# 6_Power_Fuse_MCU.net
KiCad netlist of a schematic drawn in Altium Designer
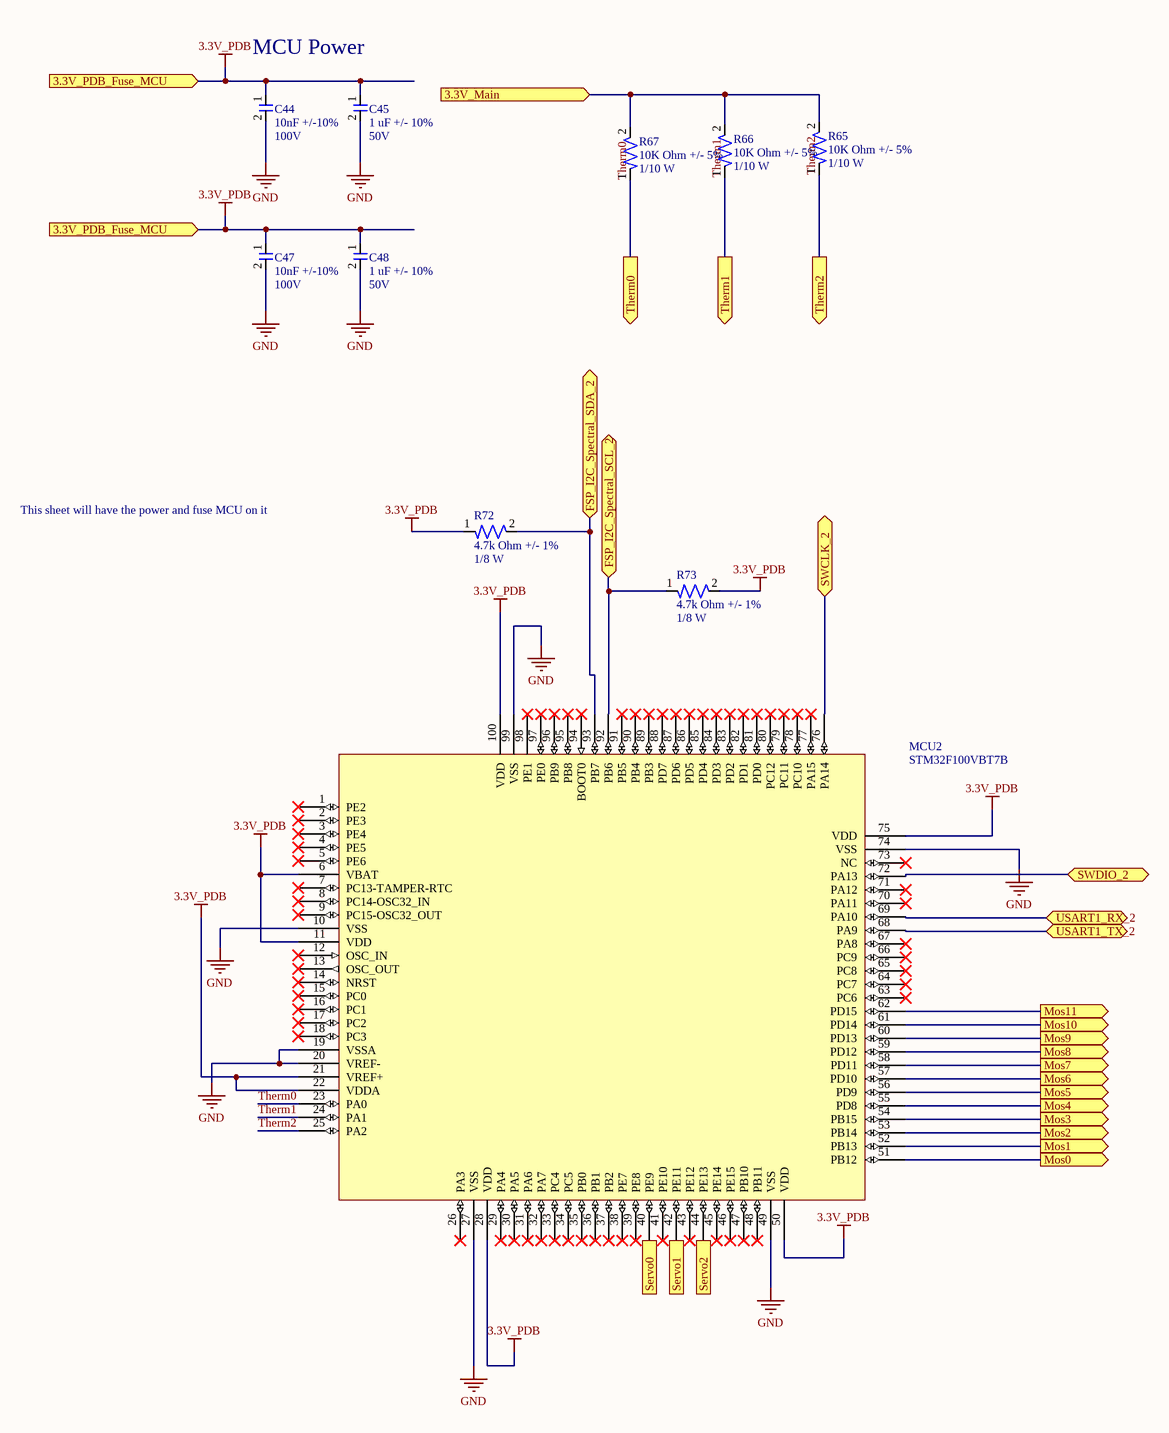
[diagram p0: 6_Power_Fuse_MCU.SchDoc]

(export (version "E")
  (design (tool "Eeschema 10.0.6"))
  (components
    (comp (ref "C44")
      (value "CC0603KRX7R0BB103")
      (footprint "CAP-0603")
      (description "100V 10nF X7R ±10% 0603 Multilayer Ceramic Capacitors MLCC - SMD/SMT ROHS")
      (fields
        (field (name "MANUFACTURER") "Yageo")
        (field (name "JLC PART NUMBER") "C107059")
        (field (name "CAPACITANCE") "10nF +/-10%")
        (field (name "VOLTAGE RATING") "100V")
      )
      (libsource (lib "MasterLib") (part "CAP-10N-0003-JLC"))
    )
    (comp (ref "C45")
      (value "GCM21BR71H105KA03L")
      (footprint "CAP-0805")
      (description "50V 1uF X7R ±10% 0805 Multilayer Ceramic Capacitors MLCC - SMD/SMT ROHS")
      (fields
        (field (name "JLC PART NUMBER") "C126592")
        (field (name "CAP") "1 uF +/- 10%")
        (field (name "VOLTAGE") "50V")
      )
      (libsource (lib "MasterLib") (part "CAP-1U-0003-JLC"))
    )
    (comp (ref "C47")
      (value "CC0603KRX7R0BB103")
      (footprint "CAP-0603")
      (description "100V 10nF X7R ±10% 0603 Multilayer Ceramic Capacitors MLCC - SMD/SMT ROHS")
      (fields
        (field (name "MANUFACTURER") "Yageo")
        (field (name "JLC PART NUMBER") "C107059")
        (field (name "CAPACITANCE") "10nF +/-10%")
        (field (name "VOLTAGE RATING") "100V")
      )
      (libsource (lib "MasterLib") (part "CAP-10N-0003-JLC"))
    )
    (comp (ref "C48")
      (value "GCM21BR71H105KA03L")
      (footprint "CAP-0805")
      (description "50V 1uF X7R ±10% 0805 Multilayer Ceramic Capacitors MLCC - SMD/SMT ROHS")
      (fields
        (field (name "JLC PART NUMBER") "C126592")
        (field (name "CAP") "1 uF +/- 10%")
        (field (name "VOLTAGE") "50V")
      )
      (libsource (lib "MasterLib") (part "CAP-1U-0003-JLC"))
    )
    (comp (ref "MCU2")
      (value "STM32F100VBT7B")
      (footprint "IC-STM32F100-0001")
      (libsource (lib "MasterLib") (part "IC-STM32F100-0001"))
    )
    (comp (ref "R65")
      (value "ERJ2GEJ103X")
      (footprint "RES-0402")
      (fields
        (field (name "RESISTANCE") "10K Ohm +/- 5%")
        (field (name "POWER") "1/10 W")
        (field (name "JLC PART NUMBER") "C278577")
      )
      (libsource (lib "MasterLib") (part "RES-10K-0003-JLC"))
    )
    (comp (ref "R66")
      (value "ERJ2GEJ103X")
      (footprint "RES-0402")
      (fields
        (field (name "RESISTANCE") "10K Ohm +/- 5%")
        (field (name "POWER") "1/10 W")
        (field (name "JLC PART NUMBER") "C278577")
      )
      (libsource (lib "MasterLib") (part "RES-10K-0003-JLC"))
    )
    (comp (ref "R67")
      (value "ERJ2GEJ103X")
      (footprint "RES-0402")
      (fields
        (field (name "RESISTANCE") "10K Ohm +/- 5%")
        (field (name "POWER") "1/10 W")
        (field (name "JLC PART NUMBER") "C278577")
      )
      (libsource (lib "MasterLib") (part "RES-10K-0003-JLC"))
    )
    (comp (ref "R72")
      (value "RC0402FR-7W4K7L")
      (footprint "RES-0402")
      (fields
        (field (name "RESISTANCE") "4.7k Ohm +/- 1%")
        (field (name "POWER") "1/8 W")
        (field (name "JLC PART NUMBER") "C606173")
      )
      (libsource (lib "MasterLib") (part "RES-4.7K-0003-JLC"))
    )
    (comp (ref "R73")
      (value "RC0402FR-7W4K7L")
      (footprint "RES-0402")
      (fields
        (field (name "RESISTANCE") "4.7k Ohm +/- 1%")
        (field (name "POWER") "1/8 W")
        (field (name "JLC PART NUMBER") "C606173")
      )
      (libsource (lib "MasterLib") (part "RES-4.7K-0003-JLC"))
    )
  )
  (nets
    (net (code "1") (name "/3.3V_Main") (class "Default")
      (node (ref "R65") (pin "2") (pinfunction "2_2") (pintype "passive"))
      (node (ref "R66") (pin "2") (pinfunction "2_2") (pintype "passive"))
      (node (ref "R67") (pin "2") (pinfunction "2_2") (pintype "passive"))
    )
    (net (code "2") (name "/FSP_I2C_Spectral_SCL_2") (class "Default")
      (node (ref "MCU2") (pin "92") (pinfunction "PB6_92") (pintype "bidirectional"))
      (node (ref "R73") (pin "1") (pinfunction "1_1") (pintype "passive"))
    )
    (net (code "3") (name "/FSP_I2C_Spectral_SDA_2") (class "Default")
      (node (ref "MCU2") (pin "93") (pinfunction "PB7_93") (pintype "bidirectional"))
      (node (ref "R72") (pin "2") (pinfunction "2_2") (pintype "passive"))
    )
    (net (code "4") (name "/Mos0") (class "Default")
      (node (ref "MCU2") (pin "51") (pinfunction "PB12_51") (pintype "bidirectional"))
    )
    (net (code "5") (name "/Mos1") (class "Default")
      (node (ref "MCU2") (pin "52") (pinfunction "PB13_52") (pintype "bidirectional"))
    )
    (net (code "6") (name "/Mos2") (class "Default")
      (node (ref "MCU2") (pin "53") (pinfunction "PB14_53") (pintype "bidirectional"))
    )
    (net (code "7") (name "/Mos3") (class "Default")
      (node (ref "MCU2") (pin "54") (pinfunction "PB15_54") (pintype "bidirectional"))
    )
    (net (code "8") (name "/Mos4") (class "Default")
      (node (ref "MCU2") (pin "55") (pinfunction "PD8_55") (pintype "bidirectional"))
    )
    (net (code "9") (name "/Mos5") (class "Default")
      (node (ref "MCU2") (pin "56") (pinfunction "PD9_56") (pintype "bidirectional"))
    )
    (net (code "10") (name "/Mos6") (class "Default")
      (node (ref "MCU2") (pin "57") (pinfunction "PD10_57") (pintype "bidirectional"))
    )
    (net (code "11") (name "/Mos7") (class "Default")
      (node (ref "MCU2") (pin "58") (pinfunction "PD11_58") (pintype "bidirectional"))
    )
    (net (code "12") (name "/Mos8") (class "Default")
      (node (ref "MCU2") (pin "59") (pinfunction "PD12_59") (pintype "bidirectional"))
    )
    (net (code "13") (name "/Mos9") (class "Default")
      (node (ref "MCU2") (pin "60") (pinfunction "PD13_60") (pintype "bidirectional"))
    )
    (net (code "14") (name "/Mos10") (class "Default")
      (node (ref "MCU2") (pin "61") (pinfunction "PD14_61") (pintype "bidirectional"))
    )
    (net (code "15") (name "/Mos11") (class "Default")
      (node (ref "MCU2") (pin "62") (pinfunction "PD15_62") (pintype "bidirectional"))
    )
    (net (code "16") (name "/SWCLK_2") (class "Default")
      (node (ref "MCU2") (pin "76") (pinfunction "PA14_76") (pintype "bidirectional"))
    )
    (net (code "17") (name "/SWDIO_2") (class "Default")
      (node (ref "MCU2") (pin "72") (pinfunction "PA13_72") (pintype "bidirectional"))
    )
    (net (code "18") (name "/Servo0") (class "Default")
      (node (ref "MCU2") (pin "40") (pinfunction "PE9_40") (pintype "bidirectional"))
    )
    (net (code "19") (name "/Servo1") (class "Default")
      (node (ref "MCU2") (pin "42") (pinfunction "PE11_42") (pintype "bidirectional"))
    )
    (net (code "20") (name "/Servo2") (class "Default")
      (node (ref "MCU2") (pin "44") (pinfunction "PE13_44") (pintype "bidirectional"))
    )
    (net (code "21") (name "/Therm0") (class "Default")
      (node (ref "MCU2") (pin "23") (pinfunction "PA0_23") (pintype "bidirectional"))
      (node (ref "R67") (pin "1") (pinfunction "1_1") (pintype "passive"))
    )
    (net (code "22") (name "/Therm1") (class "Default")
      (node (ref "MCU2") (pin "24") (pinfunction "PA1_24") (pintype "bidirectional"))
      (node (ref "R66") (pin "1") (pinfunction "1_1") (pintype "passive"))
    )
    (net (code "23") (name "/Therm2") (class "Default")
      (node (ref "MCU2") (pin "25") (pinfunction "PA2_25") (pintype "bidirectional"))
      (node (ref "R65") (pin "1") (pinfunction "1_1") (pintype "passive"))
    )
    (net (code "24") (name "/USART1_RX_2") (class "Default")
      (node (ref "MCU2") (pin "69") (pinfunction "PA10_69") (pintype "bidirectional"))
    )
    (net (code "25") (name "/USART1_TX_2") (class "Default")
      (node (ref "MCU2") (pin "68") (pinfunction "PA9_68") (pintype "bidirectional"))
    )
    (net (code "26") (name "3.3V_PDB") (class "Default")
      (node (ref "C44") (pin "1") (pinfunction "1_1") (pintype "passive"))
      (node (ref "C45") (pin "1") (pinfunction "1_1") (pintype "passive"))
      (node (ref "C47") (pin "1") (pinfunction "1_1") (pintype "passive"))
      (node (ref "C48") (pin "1") (pinfunction "1_1") (pintype "passive"))
      (node (ref "MCU2") (pin "100") (pinfunction "VDD_100") (pintype "power_in"))
      (node (ref "MCU2") (pin "11") (pinfunction "VDD_11") (pintype "power_in"))
      (node (ref "MCU2") (pin "21") (pinfunction "VREF+_21") (pintype "power_in"))
      (node (ref "MCU2") (pin "22") (pinfunction "VDDA_22") (pintype "power_in"))
      (node (ref "MCU2") (pin "28") (pinfunction "VDD_28") (pintype "power_in"))
      (node (ref "MCU2") (pin "50") (pinfunction "VDD_50") (pintype "power_in"))
      (node (ref "MCU2") (pin "6") (pinfunction "VBAT_6") (pintype "power_in"))
      (node (ref "MCU2") (pin "75") (pinfunction "VDD_75") (pintype "power_in"))
      (node (ref "R72") (pin "1") (pinfunction "1_1") (pintype "passive"))
      (node (ref "R73") (pin "2") (pinfunction "2_2") (pintype "passive"))
    )
    (net (code "27") (name "GND") (class "Default")
      (node (ref "C44") (pin "2") (pinfunction "2_2") (pintype "passive"))
      (node (ref "C45") (pin "2") (pinfunction "2_2") (pintype "passive"))
      (node (ref "C47") (pin "2") (pinfunction "2_2") (pintype "passive"))
      (node (ref "C48") (pin "2") (pinfunction "2_2") (pintype "passive"))
      (node (ref "MCU2") (pin "10") (pinfunction "VSS_10") (pintype "power_in"))
      (node (ref "MCU2") (pin "19") (pinfunction "VSSA_19") (pintype "power_in"))
      (node (ref "MCU2") (pin "20") (pinfunction "VREF-_20") (pintype "power_in"))
      (node (ref "MCU2") (pin "27") (pinfunction "VSS_27") (pintype "power_in"))
      (node (ref "MCU2") (pin "49") (pinfunction "VSS_49") (pintype "power_in"))
      (node (ref "MCU2") (pin "74") (pinfunction "VSS_74") (pintype "power_in"))
      (node (ref "MCU2") (pin "99") (pinfunction "VSS_99") (pintype "power_in"))
    )
    (net (code "28") (name "unconnected-(MCU2-BOOT0-Pad94)") (class "Default")
      (node (ref "MCU2") (pin "94") (pinfunction "BOOT0_94") (pintype "input+no_connect"))
    )
    (net (code "29") (name "unconnected-(MCU2-NC-Pad73)") (class "Default")
      (node (ref "MCU2") (pin "73") (pinfunction "NC_73") (pintype "bidirectional+no_connect"))
    )
    (net (code "30") (name "unconnected-(MCU2-NRST-Pad14)") (class "Default")
      (node (ref "MCU2") (pin "14") (pinfunction "NRST_14") (pintype "bidirectional+no_connect"))
    )
    (net (code "31") (name "unconnected-(MCU2-OSC_IN-Pad12)") (class "Default")
      (node (ref "MCU2") (pin "12") (pinfunction "OSC_IN_12") (pintype "input+no_connect"))
    )
    (net (code "32") (name "unconnected-(MCU2-OSC_OUT-Pad13)") (class "Default")
      (node (ref "MCU2") (pin "13") (pinfunction "OSC_OUT_13") (pintype "output+no_connect"))
    )
    (net (code "33") (name "unconnected-(MCU2-PA3-Pad26)") (class "Default")
      (node (ref "MCU2") (pin "26") (pinfunction "PA3_26") (pintype "bidirectional+no_connect"))
    )
    (net (code "34") (name "unconnected-(MCU2-PA4-Pad29)") (class "Default")
      (node (ref "MCU2") (pin "29") (pinfunction "PA4_29") (pintype "bidirectional+no_connect"))
    )
    (net (code "35") (name "unconnected-(MCU2-PA5-Pad30)") (class "Default")
      (node (ref "MCU2") (pin "30") (pinfunction "PA5_30") (pintype "bidirectional+no_connect"))
    )
    (net (code "36") (name "unconnected-(MCU2-PA6-Pad31)") (class "Default")
      (node (ref "MCU2") (pin "31") (pinfunction "PA6_31") (pintype "bidirectional+no_connect"))
    )
    (net (code "37") (name "unconnected-(MCU2-PA7-Pad32)") (class "Default")
      (node (ref "MCU2") (pin "32") (pinfunction "PA7_32") (pintype "bidirectional+no_connect"))
    )
    (net (code "38") (name "unconnected-(MCU2-PA8-Pad67)") (class "Default")
      (node (ref "MCU2") (pin "67") (pinfunction "PA8_67") (pintype "bidirectional+no_connect"))
    )
    (net (code "39") (name "unconnected-(MCU2-PA11-Pad70)") (class "Default")
      (node (ref "MCU2") (pin "70") (pinfunction "PA11_70") (pintype "bidirectional+no_connect"))
    )
    (net (code "40") (name "unconnected-(MCU2-PA12-Pad71)") (class "Default")
      (node (ref "MCU2") (pin "71") (pinfunction "PA12_71") (pintype "bidirectional+no_connect"))
    )
    (net (code "41") (name "unconnected-(MCU2-PA15-Pad77)") (class "Default")
      (node (ref "MCU2") (pin "77") (pinfunction "PA15_77") (pintype "bidirectional+no_connect"))
    )
    (net (code "42") (name "unconnected-(MCU2-PB0-Pad35)") (class "Default")
      (node (ref "MCU2") (pin "35") (pinfunction "PB0_35") (pintype "bidirectional+no_connect"))
    )
    (net (code "43") (name "unconnected-(MCU2-PB1-Pad36)") (class "Default")
      (node (ref "MCU2") (pin "36") (pinfunction "PB1_36") (pintype "bidirectional+no_connect"))
    )
    (net (code "44") (name "unconnected-(MCU2-PB2-Pad37)") (class "Default")
      (node (ref "MCU2") (pin "37") (pinfunction "PB2_37") (pintype "bidirectional+no_connect"))
    )
    (net (code "45") (name "unconnected-(MCU2-PB3-Pad89)") (class "Default")
      (node (ref "MCU2") (pin "89") (pinfunction "PB3_89") (pintype "bidirectional+no_connect"))
    )
    (net (code "46") (name "unconnected-(MCU2-PB4-Pad90)") (class "Default")
      (node (ref "MCU2") (pin "90") (pinfunction "PB4_90") (pintype "bidirectional+no_connect"))
    )
    (net (code "47") (name "unconnected-(MCU2-PB5-Pad91)") (class "Default")
      (node (ref "MCU2") (pin "91") (pinfunction "PB5_91") (pintype "bidirectional+no_connect"))
    )
    (net (code "48") (name "unconnected-(MCU2-PB8-Pad95)") (class "Default")
      (node (ref "MCU2") (pin "95") (pinfunction "PB8_95") (pintype "bidirectional+no_connect"))
    )
    (net (code "49") (name "unconnected-(MCU2-PB9-Pad96)") (class "Default")
      (node (ref "MCU2") (pin "96") (pinfunction "PB9_96") (pintype "bidirectional+no_connect"))
    )
    (net (code "50") (name "unconnected-(MCU2-PB10-Pad47)") (class "Default")
      (node (ref "MCU2") (pin "47") (pinfunction "PB10_47") (pintype "bidirectional+no_connect"))
    )
    (net (code "51") (name "unconnected-(MCU2-PB11-Pad48)") (class "Default")
      (node (ref "MCU2") (pin "48") (pinfunction "PB11_48") (pintype "bidirectional+no_connect"))
    )
    (net (code "52") (name "unconnected-(MCU2-PC0-Pad15)") (class "Default")
      (node (ref "MCU2") (pin "15") (pinfunction "PC0_15") (pintype "bidirectional+no_connect"))
    )
    (net (code "53") (name "unconnected-(MCU2-PC1-Pad16)") (class "Default")
      (node (ref "MCU2") (pin "16") (pinfunction "PC1_16") (pintype "bidirectional+no_connect"))
    )
    (net (code "54") (name "unconnected-(MCU2-PC2-Pad17)") (class "Default")
      (node (ref "MCU2") (pin "17") (pinfunction "PC2_17") (pintype "bidirectional+no_connect"))
    )
    (net (code "55") (name "unconnected-(MCU2-PC3-Pad18)") (class "Default")
      (node (ref "MCU2") (pin "18") (pinfunction "PC3_18") (pintype "bidirectional+no_connect"))
    )
    (net (code "56") (name "unconnected-(MCU2-PC4-Pad33)") (class "Default")
      (node (ref "MCU2") (pin "33") (pinfunction "PC4_33") (pintype "bidirectional+no_connect"))
    )
    (net (code "57") (name "unconnected-(MCU2-PC5-Pad34)") (class "Default")
      (node (ref "MCU2") (pin "34") (pinfunction "PC5_34") (pintype "bidirectional+no_connect"))
    )
    (net (code "58") (name "unconnected-(MCU2-PC6-Pad63)") (class "Default")
      (node (ref "MCU2") (pin "63") (pinfunction "PC6_63") (pintype "bidirectional+no_connect"))
    )
    (net (code "59") (name "unconnected-(MCU2-PC7-Pad64)") (class "Default")
      (node (ref "MCU2") (pin "64") (pinfunction "PC7_64") (pintype "bidirectional+no_connect"))
    )
    (net (code "60") (name "unconnected-(MCU2-PC8-Pad65)") (class "Default")
      (node (ref "MCU2") (pin "65") (pinfunction "PC8_65") (pintype "bidirectional+no_connect"))
    )
    (net (code "61") (name "unconnected-(MCU2-PC9-Pad66)") (class "Default")
      (node (ref "MCU2") (pin "66") (pinfunction "PC9_66") (pintype "bidirectional+no_connect"))
    )
    (net (code "62") (name "unconnected-(MCU2-PC10-Pad78)") (class "Default")
      (node (ref "MCU2") (pin "78") (pinfunction "PC10_78") (pintype "bidirectional+no_connect"))
    )
    (net (code "63") (name "unconnected-(MCU2-PC11-Pad79)") (class "Default")
      (node (ref "MCU2") (pin "79") (pinfunction "PC11_79") (pintype "bidirectional+no_connect"))
    )
    (net (code "64") (name "unconnected-(MCU2-PC12-Pad80)") (class "Default")
      (node (ref "MCU2") (pin "80") (pinfunction "PC12_80") (pintype "bidirectional+no_connect"))
    )
    (net (code "65") (name "unconnected-(MCU2-PC13-TAMPER-RTC-Pad7)") (class "Default")
      (node (ref "MCU2") (pin "7") (pinfunction "PC13-TAMPER-RTC_7") (pintype "bidirectional+no_connect"))
    )
    (net (code "66") (name "unconnected-(MCU2-PC14-OSC32_IN-Pad8)") (class "Default")
      (node (ref "MCU2") (pin "8") (pinfunction "PC14-OSC32_IN_8") (pintype "bidirectional+no_connect"))
    )
    (net (code "67") (name "unconnected-(MCU2-PC15-OSC32_OUT-Pad9)") (class "Default")
      (node (ref "MCU2") (pin "9") (pinfunction "PC15-OSC32_OUT_9") (pintype "bidirectional+no_connect"))
    )
    (net (code "68") (name "unconnected-(MCU2-PD0-Pad81)") (class "Default")
      (node (ref "MCU2") (pin "81") (pinfunction "PD0_81") (pintype "bidirectional+no_connect"))
    )
    (net (code "69") (name "unconnected-(MCU2-PD1-Pad82)") (class "Default")
      (node (ref "MCU2") (pin "82") (pinfunction "PD1_82") (pintype "bidirectional+no_connect"))
    )
    (net (code "70") (name "unconnected-(MCU2-PD2-Pad83)") (class "Default")
      (node (ref "MCU2") (pin "83") (pinfunction "PD2_83") (pintype "bidirectional+no_connect"))
    )
    (net (code "71") (name "unconnected-(MCU2-PD3-Pad84)") (class "Default")
      (node (ref "MCU2") (pin "84") (pinfunction "PD3_84") (pintype "bidirectional+no_connect"))
    )
    (net (code "72") (name "unconnected-(MCU2-PD4-Pad85)") (class "Default")
      (node (ref "MCU2") (pin "85") (pinfunction "PD4_85") (pintype "bidirectional+no_connect"))
    )
    (net (code "73") (name "unconnected-(MCU2-PD5-Pad86)") (class "Default")
      (node (ref "MCU2") (pin "86") (pinfunction "PD5_86") (pintype "bidirectional+no_connect"))
    )
    (net (code "74") (name "unconnected-(MCU2-PD6-Pad87)") (class "Default")
      (node (ref "MCU2") (pin "87") (pinfunction "PD6_87") (pintype "bidirectional+no_connect"))
    )
    (net (code "75") (name "unconnected-(MCU2-PD7-Pad88)") (class "Default")
      (node (ref "MCU2") (pin "88") (pinfunction "PD7_88") (pintype "bidirectional+no_connect"))
    )
    (net (code "76") (name "unconnected-(MCU2-PE0-Pad97)") (class "Default")
      (node (ref "MCU2") (pin "97") (pinfunction "PE0_97") (pintype "bidirectional+no_connect"))
    )
    (net (code "77") (name "unconnected-(MCU2-PE1-Pad98)") (class "Default")
      (node (ref "MCU2") (pin "98") (pinfunction "PE1_98") (pintype "power_in+no_connect"))
    )
    (net (code "78") (name "unconnected-(MCU2-PE2-Pad1)") (class "Default")
      (node (ref "MCU2") (pin "1") (pinfunction "PE2_1") (pintype "bidirectional+no_connect"))
    )
    (net (code "79") (name "unconnected-(MCU2-PE3-Pad2)") (class "Default")
      (node (ref "MCU2") (pin "2") (pinfunction "PE3_2") (pintype "bidirectional+no_connect"))
    )
    (net (code "80") (name "unconnected-(MCU2-PE4-Pad3)") (class "Default")
      (node (ref "MCU2") (pin "3") (pinfunction "PE4_3") (pintype "bidirectional+no_connect"))
    )
    (net (code "81") (name "unconnected-(MCU2-PE5-Pad4)") (class "Default")
      (node (ref "MCU2") (pin "4") (pinfunction "PE5_4") (pintype "bidirectional+no_connect"))
    )
    (net (code "82") (name "unconnected-(MCU2-PE6-Pad5)") (class "Default")
      (node (ref "MCU2") (pin "5") (pinfunction "PE6_5") (pintype "bidirectional+no_connect"))
    )
    (net (code "83") (name "unconnected-(MCU2-PE7-Pad38)") (class "Default")
      (node (ref "MCU2") (pin "38") (pinfunction "PE7_38") (pintype "bidirectional+no_connect"))
    )
    (net (code "84") (name "unconnected-(MCU2-PE8-Pad39)") (class "Default")
      (node (ref "MCU2") (pin "39") (pinfunction "PE8_39") (pintype "bidirectional+no_connect"))
    )
    (net (code "85") (name "unconnected-(MCU2-PE10-Pad41)") (class "Default")
      (node (ref "MCU2") (pin "41") (pinfunction "PE10_41") (pintype "bidirectional+no_connect"))
    )
    (net (code "86") (name "unconnected-(MCU2-PE12-Pad43)") (class "Default")
      (node (ref "MCU2") (pin "43") (pinfunction "PE12_43") (pintype "bidirectional+no_connect"))
    )
    (net (code "87") (name "unconnected-(MCU2-PE14-Pad45)") (class "Default")
      (node (ref "MCU2") (pin "45") (pinfunction "PE14_45") (pintype "bidirectional+no_connect"))
    )
    (net (code "88") (name "unconnected-(MCU2-PE15-Pad46)") (class "Default")
      (node (ref "MCU2") (pin "46") (pinfunction "PE15_46") (pintype "bidirectional+no_connect"))
    )
  )
)
